# B293A_DAC.net
KiCad netlist of a schematic drawn in Altium Designer
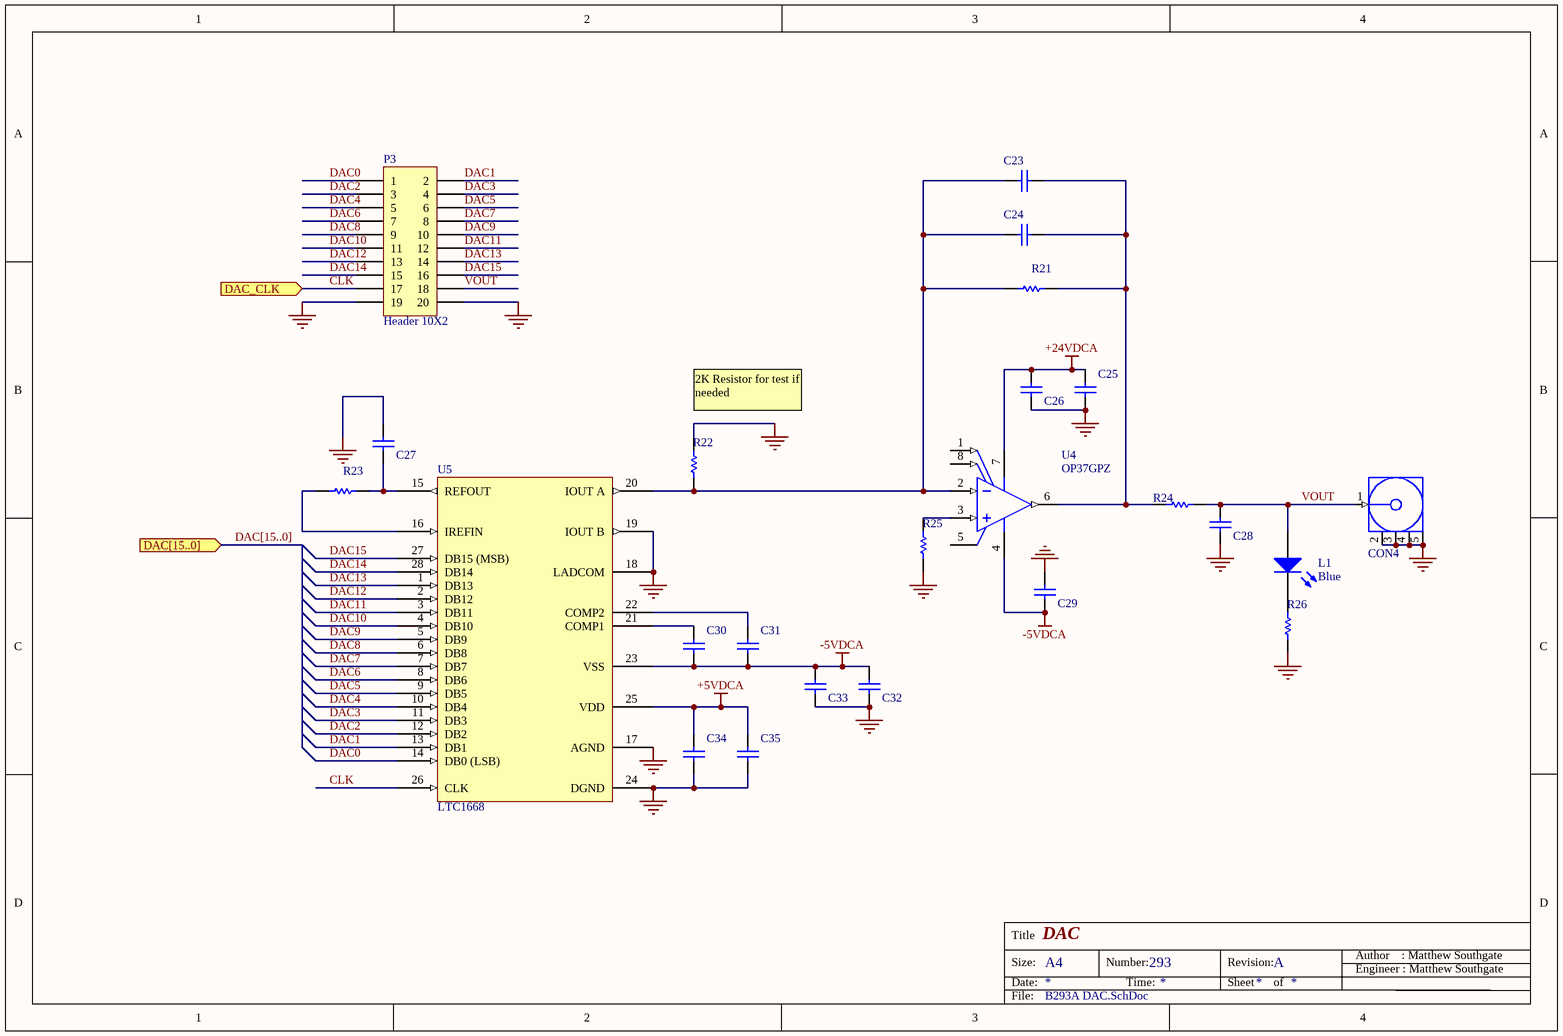
[diagram p0: B293A DAC.SchDoc]

(export (version "E")
  (design (tool "Eeschema 10.0.6"))
  (components
    (comp (ref "C23")
      (value "CAP 4.7nF 50V 0805(2012)")
      (footprint "CAPC0805(2012)75_M")
      (description "CAP 4.7nF 50V ±10% 0805 (2012 Metric) Thickness 0.75mm SMD")
      (fields (field (name "TOLERANCE") "±10%"))
      (libsource (lib "Altium Content Vault") (part "CAP"))
    )
    (comp (ref "C24")
      (value "CAP 470pF 50V 0805(2012)")
      (footprint "CAPC0805(2012)100_M")
      (description "CAP 470pF 50V ±10% 0805 (2012 Metric) Thickness 1mm SMD")
      (fields (field (name "TOLERANCE") "±10%"))
      (libsource (lib "Altium Content Vault") (part "CAP"))
    )
    (comp (ref "C25")
      (value "CAP 10uF 25V 0805(2012)")
      (footprint "CAPC0805(2012)145_N")
      (description "CAP 10uF 25V ±20% 0805 (2012 Metric) Thickness 1.45mm SMD")
      (fields (field (name "TOLERANCE") "±20%"))
      (libsource (lib "Altium Content Vault") (part "CAP"))
    )
    (comp (ref "C26")
      (value "CAP 100nF 50V 0805(2012)")
      (footprint "CAPC0805(2012)100_M")
      (description "CAP 100nF 50V ±20% 0805 (2012 Metric) Thickness 1mm SMD")
      (fields (field (name "TOLERANCE") "±20%"))
      (libsource (lib "Altium Content Vault") (part "CAP"))
    )
    (comp (ref "C27")
      (value "CAP 100nF 50V 0805(2012)")
      (footprint "CAPC0805(2012)100_M")
      (description "CAP 100nF 50V ±20% 0805 (2012 Metric) Thickness 1mm SMD")
      (fields (field (name "TOLERANCE") "±20%"))
      (libsource (lib "Altium Content Vault") (part "CAP"))
    )
    (comp (ref "C28")
      (value "CAP 100nF 50V 0805(2012)")
      (footprint "CAPC0805(2012)100_M")
      (description "CAP 100nF 50V ±20% 0805 (2012 Metric) Thickness 1mm SMD")
      (fields (field (name "TOLERANCE") "±20%"))
      (libsource (lib "Altium Content Vault") (part "CAP"))
    )
    (comp (ref "C29")
      (value "CAP 100nF 50V 0805(2012)")
      (footprint "CAPC0805(2012)100_M")
      (description "CAP 100nF 50V ±20% 0805 (2012 Metric) Thickness 1mm SMD")
      (fields (field (name "TOLERANCE") "±20%"))
      (libsource (lib "Altium Content Vault") (part "CAP"))
    )
    (comp (ref "C30")
      (value "CAP 100nF 50V 0805(2012)")
      (footprint "CAPC0805(2012)100_M")
      (description "CAP 100nF 50V ±20% 0805 (2012 Metric) Thickness 1mm SMD")
      (fields (field (name "TOLERANCE") "±20%"))
      (libsource (lib "Altium Content Vault") (part "CAP"))
    )
    (comp (ref "C31")
      (value "CAP 100nF 50V 0805(2012)")
      (footprint "CAPC0805(2012)100_M")
      (description "CAP 100nF 50V ±20% 0805 (2012 Metric) Thickness 1mm SMD")
      (fields (field (name "TOLERANCE") "±20%"))
      (libsource (lib "Altium Content Vault") (part "CAP"))
    )
    (comp (ref "C32")
      (value "CAP 10uF 25V 0805(2012)")
      (footprint "CAPC0805(2012)145_N")
      (description "CAP 10uF 25V ±20% 0805 (2012 Metric) Thickness 1.45mm SMD")
      (fields (field (name "TOLERANCE") "±20%"))
      (libsource (lib "Altium Content Vault") (part "CAP"))
    )
    (comp (ref "C33")
      (value "CAP 100nF 50V 0805(2012)")
      (footprint "CAPC0805(2012)100_M")
      (description "CAP 100nF 50V ±20% 0805 (2012 Metric) Thickness 1mm SMD")
      (fields (field (name "TOLERANCE") "±20%"))
      (libsource (lib "Altium Content Vault") (part "CAP"))
    )
    (comp (ref "C34")
      (value "CAP 100nF 50V 0805(2012)")
      (footprint "CAPC0805(2012)100_M")
      (description "CAP 100nF 50V ±20% 0805 (2012 Metric) Thickness 1mm SMD")
      (fields (field (name "TOLERANCE") "±20%"))
      (libsource (lib "Altium Content Vault") (part "CAP"))
    )
    (comp (ref "C35")
      (value "CAP 10uF 25V 0805(2012)")
      (footprint "CAPC0805(2012)145_N")
      (description "CAP 10uF 25V ±20% 0805 (2012 Metric) Thickness 1.45mm SMD")
      (fields (field (name "TOLERANCE") "±20%"))
      (libsource (lib "Altium Content Vault") (part "CAP"))
    )
    (comp (ref "CON4")
      (value "SMA Vertical")
      (footprint "Matt PCB Library:SMA Vertical")
      (fields (field (name "MANUFACTURERS PART NO") "5-1814832-1"))
      (libsource (lib "Matt SCH Library") (part "SMA Vertical"))
    )
    (comp (ref "L1")
      (value "Blue")
      (footprint "Matt PCB Library:1206 - LED")
      (description "LED, 1206, BLUE, 140MCD, 473NM")
      (fields
        (field (name "MANUFACTURER PART NUMBER") "598-8291-107F")
        (field (name "MANUFACTURER") "DIALIGHT")
      )
      (libsource (lib "Matt SCH Library") (part "LED 1206 BLUE"))
    )
    (comp (ref "P3")
      (value "Header 10X2")
      (footprint "HDR2X10")
      (description "Header, 10-Pin, Dual row")
      (fields (field (name "PUBLISHER") "Altium Limited"))
      (libsource (lib "Miscellaneous Connectors") (part "Header 10X2"))
    )
    (comp (ref "R21")
      (value "2K2 5% 0805(2012)")
      (footprint "RESC0805(2012)_L")
      (description "2K2 0.125W 5% 0805 (2012 Metric)  SMD")
      (fields (field (name "TOLERANCE") "5 %") (field (name "POWER") "0.125 W"))
      (libsource (lib "Altium Content Vault") (part "RES"))
    )
    (comp (ref "R22")
      (value "2K2 5% 0805(2012)")
      (footprint "RESC0805(2012)_L")
      (description "2K2 0.125W 5% 0805 (2012 Metric)  SMD")
      (fields (field (name "TOLERANCE") "5 %") (field (name "POWER") "0.125 W"))
      (libsource (lib "Altium Content Vault") (part "RES"))
    )
    (comp (ref "R23")
      (value "2K2 5% 0805(2012)")
      (footprint "RESC0805(2012)_L")
      (description "2K2 0.125W 5% 0805 (2012 Metric)  SMD")
      (fields (field (name "TOLERANCE") "5 %") (field (name "POWER") "0.125 W"))
      (libsource (lib "Altium Content Vault") (part "RES"))
    )
    (comp (ref "R24")
      (value "150R 5% 0805(2012)")
      (footprint "RESC0805(2012)_N")
      (description "150R 0.125W 5% 0805 (2012 Metric)  SMD")
      (fields (field (name "TOLERANCE") "5 %") (field (name "POWER") "0.125 W"))
      (libsource (lib "Altium Content Vault") (part "RES"))
    )
    (comp (ref "R25")
      (value "2K2 5% 0805(2012)")
      (footprint "RESC0805(2012)_L")
      (description "2K2 0.125W 5% 0805 (2012 Metric)  SMD")
      (fields (field (name "TOLERANCE") "5 %") (field (name "POWER") "0.125 W"))
      (libsource (lib "Altium Content Vault") (part "RES"))
    )
    (comp (ref "R26")
      (value "6K8 5% 0805(2012)")
      (footprint "RESC0805(2012)_L")
      (description "6K8 0.125W 5% 0805 (2012 Metric)  SMD")
      (fields (field (name "TOLERANCE") "5 %") (field (name "POWER") "0.125 W"))
      (libsource (lib "Altium Content Vault") (part "RES"))
    )
    (comp (ref "U4")
      (value "OP37GPZ")
      (footprint "ADI-N-8")
      (fields (field (name "MANUFACTURER") "Analog Devices"))
      (libsource (lib "Altium Content Vault") (part "ADI-OP177_X7-8"))
    )
    (comp (ref "U5")
      (value "LTC1668")
      (footprint "Matt PCB Library:SOP65P800X200-28N")
      (fields
        (field (name "MANUFACTURER") "LINEAR TECHNOLOGY")
        (field (name "MANUFACTURER PART NUMBER") "LTC1668CG#PBF")
      )
      (libsource (lib "Matt SCH Library") (part "LTC1668"))
    )
  )
  (nets
    (net (code "1") (name "+5VDCA") (class "Default")
      (node (ref "C34") (pin "2") (pinfunction "2_2") (pintype "passive"))
      (node (ref "C35") (pin "2") (pinfunction "2_2") (pintype "passive"))
      (node (ref "U5") (pin "25") (pinfunction "VDD_25") (pintype "power_in"))
    )
    (net (code "2") (name "+24VDCA") (class "Default")
      (node (ref "C25") (pin "2") (pinfunction "2_2") (pintype "passive"))
      (node (ref "C26") (pin "1") (pinfunction "1_1") (pintype "passive"))
      (node (ref "U4") (pin "7") (pinfunction "V+_7") (pintype "power_in"))
    )
    (net (code "3") (name "-5VDCA") (class "Default")
      (node (ref "C29") (pin "2") (pinfunction "2_2") (pintype "passive"))
      (node (ref "C30") (pin "1") (pinfunction "1_1") (pintype "passive"))
      (node (ref "C31") (pin "1") (pinfunction "1_1") (pintype "passive"))
      (node (ref "C32") (pin "1") (pinfunction "1_1") (pintype "passive"))
      (node (ref "C33") (pin "2") (pinfunction "2_2") (pintype "passive"))
      (node (ref "U4") (pin "4") (pinfunction "V-_4") (pintype "power_in"))
      (node (ref "U5") (pin "23") (pinfunction "VSS_23") (pintype "power_in"))
    )
    (net (code "4") (name "/CLK") (class "Default")
      (node (ref "P3") (pin "17") (pinfunction "17_17") (pintype "passive"))
      (node (ref "U5") (pin "26") (pinfunction "CLK_26") (pintype "input"))
    )
    (net (code "5") (name "/DAC0") (class "Default")
      (node (ref "P3") (pin "1") (pinfunction "1_1") (pintype "passive"))
      (node (ref "U5") (pin "14") (pinfunction "DB0_(LSB)_14") (pintype "input"))
    )
    (net (code "6") (name "/DAC1") (class "Default")
      (node (ref "P3") (pin "2") (pinfunction "2_2") (pintype "passive"))
      (node (ref "U5") (pin "13") (pinfunction "DB1_13") (pintype "input"))
    )
    (net (code "7") (name "/DAC2") (class "Default")
      (node (ref "P3") (pin "3") (pinfunction "3_3") (pintype "passive"))
      (node (ref "U5") (pin "12") (pinfunction "DB2_12") (pintype "input"))
    )
    (net (code "8") (name "/DAC3") (class "Default")
      (node (ref "P3") (pin "4") (pinfunction "4_4") (pintype "passive"))
      (node (ref "U5") (pin "11") (pinfunction "DB3_11") (pintype "input"))
    )
    (net (code "9") (name "/DAC4") (class "Default")
      (node (ref "P3") (pin "5") (pinfunction "5_5") (pintype "passive"))
      (node (ref "U5") (pin "10") (pinfunction "DB4_10") (pintype "input"))
    )
    (net (code "10") (name "/DAC5") (class "Default")
      (node (ref "P3") (pin "6") (pinfunction "6_6") (pintype "passive"))
      (node (ref "U5") (pin "9") (pinfunction "DB5_9") (pintype "input"))
    )
    (net (code "11") (name "/DAC6") (class "Default")
      (node (ref "P3") (pin "7") (pinfunction "7_7") (pintype "passive"))
      (node (ref "U5") (pin "8") (pinfunction "DB6_8") (pintype "input"))
    )
    (net (code "12") (name "/DAC7") (class "Default")
      (node (ref "P3") (pin "8") (pinfunction "8_8") (pintype "passive"))
      (node (ref "U5") (pin "7") (pinfunction "DB7_7") (pintype "input"))
    )
    (net (code "13") (name "/DAC8") (class "Default")
      (node (ref "P3") (pin "9") (pinfunction "9_9") (pintype "passive"))
      (node (ref "U5") (pin "6") (pinfunction "DB8_6") (pintype "input"))
    )
    (net (code "14") (name "/DAC9") (class "Default")
      (node (ref "P3") (pin "10") (pinfunction "10_10") (pintype "passive"))
      (node (ref "U5") (pin "5") (pinfunction "DB9_5") (pintype "input"))
    )
    (net (code "15") (name "/DAC10") (class "Default")
      (node (ref "P3") (pin "11") (pinfunction "11_11") (pintype "passive"))
      (node (ref "U5") (pin "4") (pinfunction "DB10_4") (pintype "input"))
    )
    (net (code "16") (name "/DAC11") (class "Default")
      (node (ref "P3") (pin "12") (pinfunction "12_12") (pintype "passive"))
      (node (ref "U5") (pin "3") (pinfunction "DB11_3") (pintype "input"))
    )
    (net (code "17") (name "/DAC12") (class "Default")
      (node (ref "P3") (pin "13") (pinfunction "13_13") (pintype "passive"))
      (node (ref "U5") (pin "2") (pinfunction "DB12_2") (pintype "input"))
    )
    (net (code "18") (name "/DAC13") (class "Default")
      (node (ref "P3") (pin "14") (pinfunction "14_14") (pintype "passive"))
      (node (ref "U5") (pin "1") (pinfunction "DB13_1") (pintype "input"))
    )
    (net (code "19") (name "/DAC14") (class "Default")
      (node (ref "P3") (pin "15") (pinfunction "15_15") (pintype "passive"))
      (node (ref "U5") (pin "28") (pinfunction "DB14_28") (pintype "input"))
    )
    (net (code "20") (name "/DAC15") (class "Default")
      (node (ref "P3") (pin "16") (pinfunction "16_16") (pintype "passive"))
      (node (ref "U5") (pin "27") (pinfunction "DB15_(MSB)_27") (pintype "input"))
    )
    (net (code "22") (name "/VOUT") (class "Default")
      (node (ref "C28") (pin "1") (pinfunction "1_1") (pintype "passive"))
      (node (ref "CON4") (pin "1") (pinfunction "Signal_1") (pintype "input"))
      (node (ref "L1") (pin "A") (pinfunction "A_A") (pintype "passive"))
      (node (ref "P3") (pin "18") (pinfunction "18_18") (pintype "passive"))
      (node (ref "R24") (pin "1") (pinfunction "1_1") (pintype "passive"))
    )
    (net (code "23") (name "GND") (class "Default")
      (node (ref "C25") (pin "1") (pinfunction "1_1") (pintype "passive"))
      (node (ref "C26") (pin "2") (pinfunction "2_2") (pintype "passive"))
      (node (ref "C27") (pin "1") (pinfunction "1_1") (pintype "passive"))
      (node (ref "C28") (pin "2") (pinfunction "2_2") (pintype "passive"))
      (node (ref "C29") (pin "1") (pinfunction "1_1") (pintype "passive"))
      (node (ref "C32") (pin "2") (pinfunction "2_2") (pintype "passive"))
      (node (ref "C33") (pin "1") (pinfunction "1_1") (pintype "passive"))
      (node (ref "C34") (pin "1") (pinfunction "1_1") (pintype "passive"))
      (node (ref "C35") (pin "1") (pinfunction "1_1") (pintype "passive"))
      (node (ref "CON4") (pin "2") (pinfunction "GND_2") (pintype "power_in"))
      (node (ref "CON4") (pin "3") (pinfunction "GND_3") (pintype "power_in"))
      (node (ref "CON4") (pin "4") (pinfunction "GND_4") (pintype "power_in"))
      (node (ref "CON4") (pin "5") (pinfunction "GND_5") (pintype "power_in"))
      (node (ref "P3") (pin "19") (pinfunction "19_19") (pintype "passive"))
      (node (ref "P3") (pin "20") (pinfunction "20_20") (pintype "passive"))
      (node (ref "R22") (pin "2") (pinfunction "2_2") (pintype "passive"))
      (node (ref "R25") (pin "1") (pinfunction "1_1") (pintype "passive"))
      (node (ref "R26") (pin "1") (pinfunction "1_1") (pintype "passive"))
      (node (ref "U5") (pin "17") (pinfunction "AGND_17") (pintype "power_in"))
      (node (ref "U5") (pin "18") (pinfunction "LADCOM_18") (pintype "power_in"))
      (node (ref "U5") (pin "19") (pinfunction "IOUT_B_19") (pintype "output"))
      (node (ref "U5") (pin "24") (pinfunction "DGND_24") (pintype "power_in"))
    )
    (net (code "24") (name "Net-(L1-PadK)") (class "Default")
      (node (ref "L1") (pin "K") (pinfunction "K_K") (pintype "passive"))
      (node (ref "R26") (pin "2") (pinfunction "2_2") (pintype "passive"))
    )
    (net (code "25") (name "Net-(U4-+IN)") (class "Default")
      (node (ref "R25") (pin "2") (pinfunction "2_2") (pintype "passive"))
      (node (ref "U4") (pin "3") (pinfunction "+IN_3") (pintype "input"))
    )
    (net (code "26") (name "Net-(U4--IN)") (class "Default")
      (node (ref "C23") (pin "2") (pinfunction "2_2") (pintype "passive"))
      (node (ref "C24") (pin "2") (pinfunction "2_2") (pintype "passive"))
      (node (ref "R21") (pin "1") (pinfunction "1_1") (pintype "passive"))
      (node (ref "R22") (pin "1") (pinfunction "1_1") (pintype "passive"))
      (node (ref "U4") (pin "2") (pinfunction "-IN_2") (pintype "input"))
      (node (ref "U5") (pin "20") (pinfunction "IOUT_A_20") (pintype "output"))
    )
    (net (code "27") (name "Net-(U4-OUT)") (class "Default")
      (node (ref "C23") (pin "1") (pinfunction "1_1") (pintype "passive"))
      (node (ref "C24") (pin "1") (pinfunction "1_1") (pintype "passive"))
      (node (ref "R21") (pin "2") (pinfunction "2_2") (pintype "passive"))
      (node (ref "R24") (pin "2") (pinfunction "2_2") (pintype "passive"))
      (node (ref "U4") (pin "6") (pinfunction "OUT_6") (pintype "output"))
    )
    (net (code "28") (name "Net-(U5-COMP1)") (class "Default")
      (node (ref "C30") (pin "2") (pinfunction "2_2") (pintype "passive"))
      (node (ref "U5") (pin "21") (pinfunction "COMP1_21") (pintype "passive"))
    )
    (net (code "29") (name "Net-(U5-COMP2)") (class "Default")
      (node (ref "C31") (pin "2") (pinfunction "2_2") (pintype "passive"))
      (node (ref "U5") (pin "22") (pinfunction "COMP2_22") (pintype "passive"))
    )
    (net (code "30") (name "Net-(U5-IREFIN)") (class "Default")
      (node (ref "R23") (pin "1") (pinfunction "1_1") (pintype "passive"))
      (node (ref "U5") (pin "16") (pinfunction "IREFIN_16") (pintype "input"))
    )
    (net (code "31") (name "Net-(U5-REFOUT)") (class "Default")
      (node (ref "C27") (pin "2") (pinfunction "2_2") (pintype "passive"))
      (node (ref "R23") (pin "2") (pinfunction "2_2") (pintype "passive"))
      (node (ref "U5") (pin "15") (pinfunction "REFOUT_15") (pintype "output"))
    )
    (net (code "32") (name "unconnected-(U4-NC-Pad5)") (class "Default")
      (node (ref "U4") (pin "5") (pinfunction "NC_5") (pintype "passive"))
    )
    (net (code "33") (name "unconnected-(U4-VOS_TRIM-Pad1)") (class "Default")
      (node (ref "U4") (pin "1") (pinfunction "VOS_TRIM_1") (pintype "input"))
    )
    (net (code "34") (name "unconnected-(U4-VOS_TRIM-Pad8)") (class "Default")
      (node (ref "U4") (pin "8") (pinfunction "VOS_TRIM_8") (pintype "input"))
    )
  )
)
